# Battery_board_V4_2.net
KiCad netlist of a schematic drawn in EAGLE
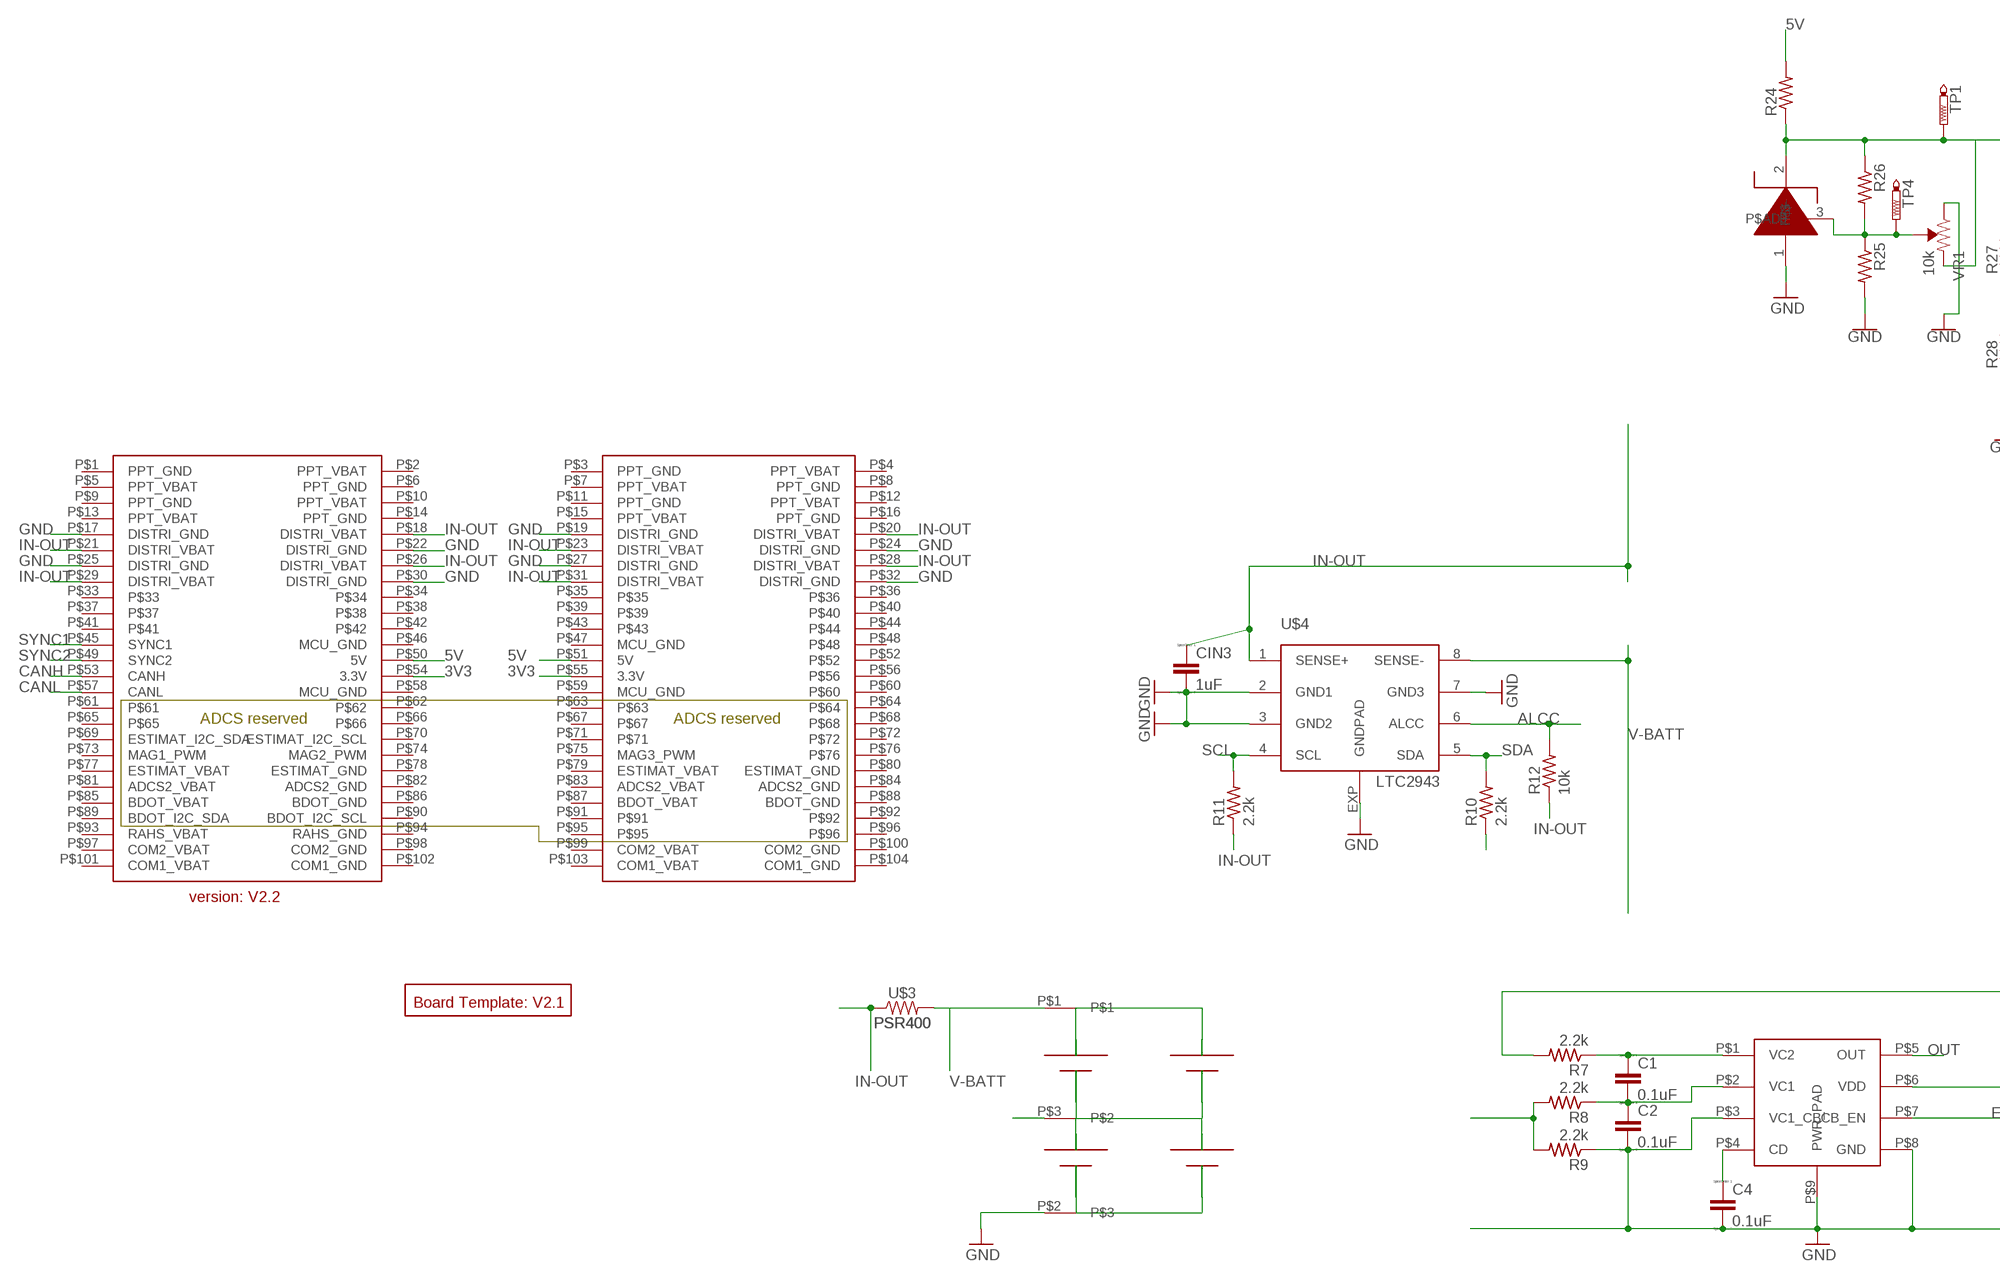
[diagram p0: schematic, sheet 1, part 1 of 2]
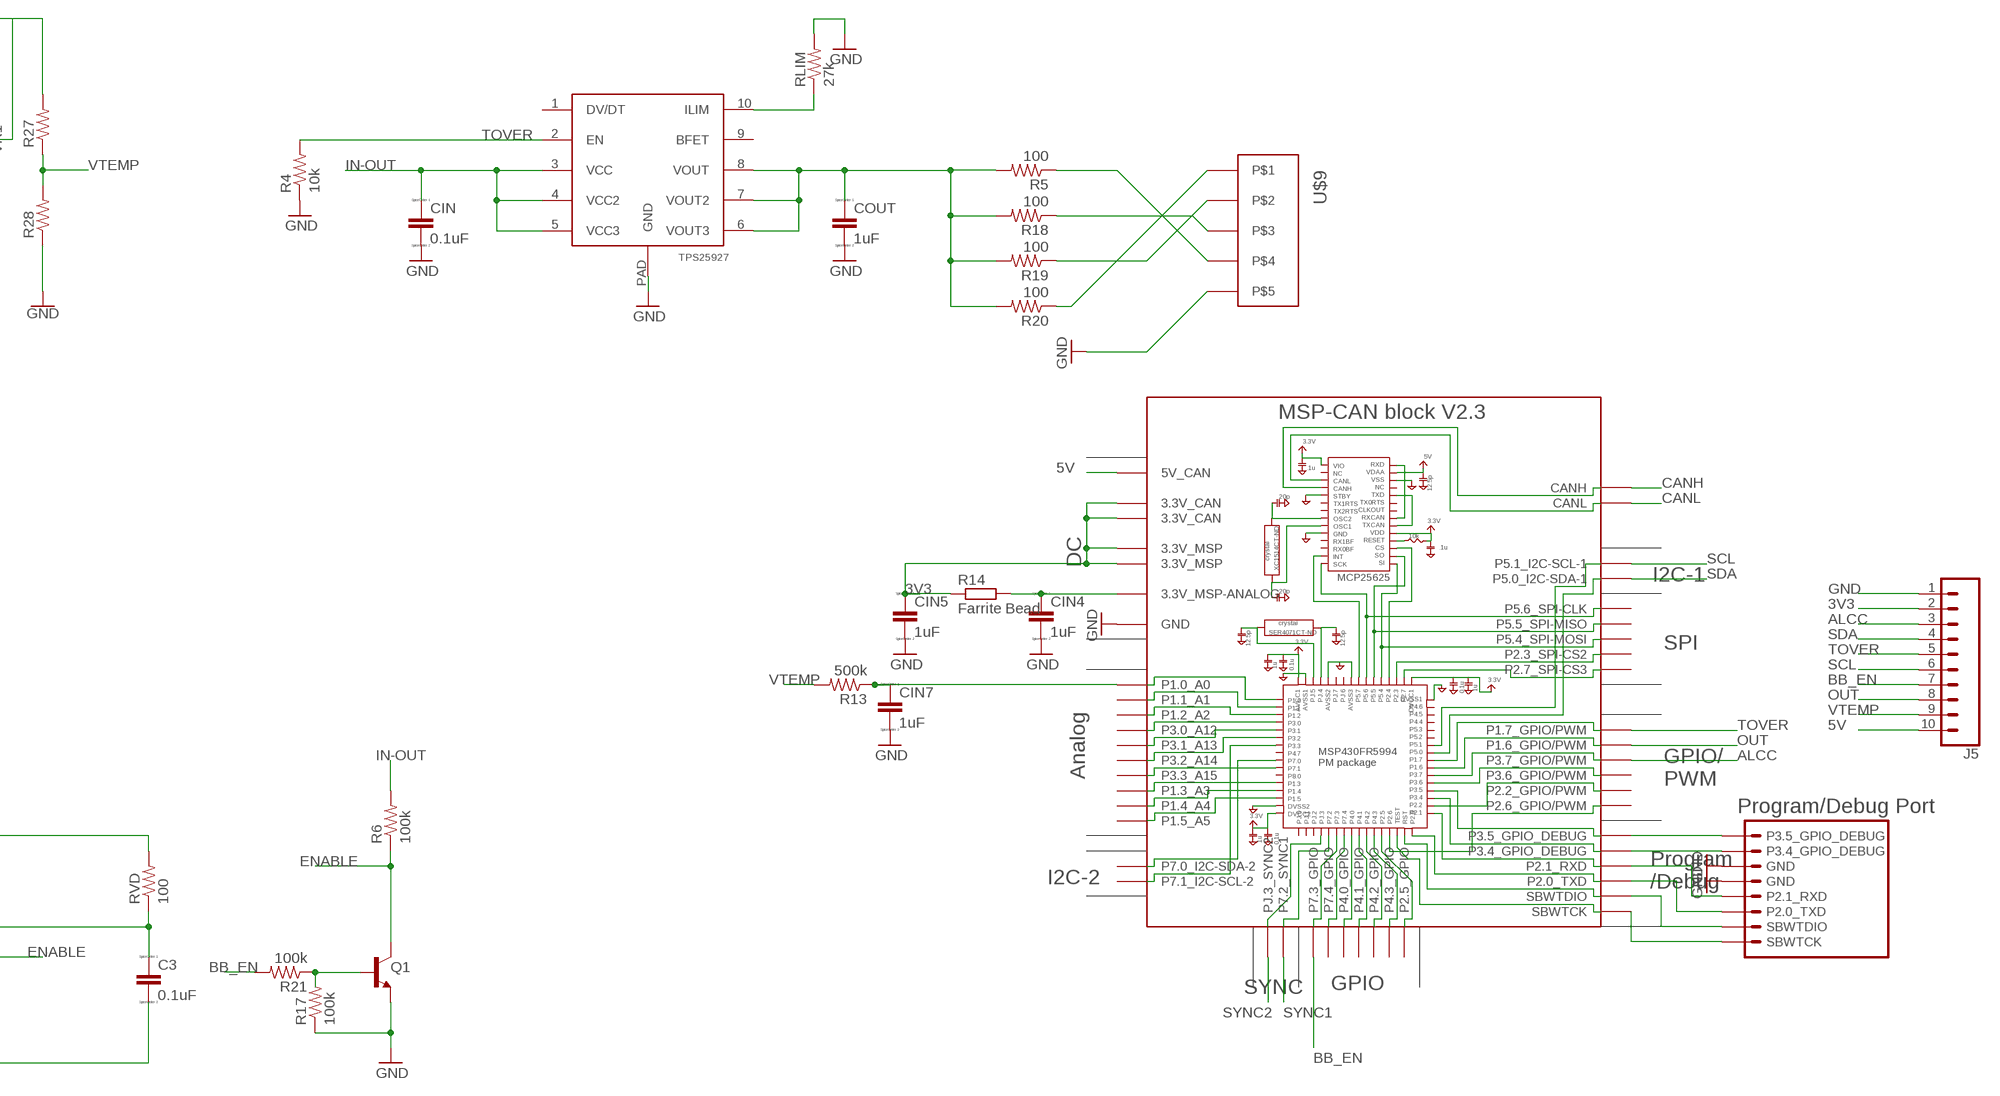
[diagram p1: schematic, sheet 1, part 2 of 2]

(export (version "E")
  (design (tool "Eeschema 10.0.6"))
  (components
    (comp (ref "C1")
      (value "0.1uF")
      (footprint "eagle-import:C0805")
      (libsource (lib "eagle-import") (part "C"))
    )
    (comp (ref "C2")
      (value "0.1uF")
      (footprint "eagle-import:C0805")
      (libsource (lib "eagle-import") (part "C"))
    )
    (comp (ref "C3")
      (value "0.1uF")
      (footprint "eagle-import:C0805")
      (libsource (lib "eagle-import") (part "C"))
    )
    (comp (ref "C4")
      (value "0.1uF")
      (footprint "eagle-import:C0805")
      (libsource (lib "eagle-import") (part "C"))
    )
    (comp (ref "CIN")
      (value "0.1uF")
      (footprint "eagle-import:C0805")
      (libsource (lib "eagle-import") (part "C"))
    )
    (comp (ref "CIN3")
      (value "1uF")
      (footprint "eagle-import:C0805")
      (libsource (lib "eagle-import") (part "C"))
    )
    (comp (ref "CIN4")
      (value "1uF")
      (footprint "eagle-import:C0805")
      (libsource (lib "eagle-import") (part "C"))
    )
    (comp (ref "CIN5")
      (value "1uF")
      (footprint "eagle-import:C0805")
      (libsource (lib "eagle-import") (part "C"))
    )
    (comp (ref "CIN7")
      (value "1uF")
      (footprint "eagle-import:C0805")
      (libsource (lib "eagle-import") (part "C"))
    )
    (comp (ref "COUT")
      (value "1uF")
      (footprint "eagle-import:C0805")
      (libsource (lib "eagle-import") (part "C"))
    )
    (comp (ref "J5")
      (value "CONN_10LOCK")
      (footprint "eagle-import:1X10_LOCK")
      (libsource (lib "eagle-import") (part "CONN_10LOCK"))
    )
    (comp (ref "Q1")
      (value "TRANS_NPN-MMBT2222AL")
      (footprint "eagle-import:SOT23-3")
      (libsource (lib "eagle-import") (part "TRANS_NPN-MMBT2222AL"))
    )
    (comp (ref "R4")
      (value "10k")
      (footprint "eagle-import:R0805")
      (libsource (lib "eagle-import") (part "R-US_R0805"))
    )
    (comp (ref "R5")
      (value "100")
      (footprint "eagle-import:R0805")
      (libsource (lib "eagle-import") (part "R-US_R0805"))
    )
    (comp (ref "R6")
      (value "100k")
      (footprint "eagle-import:R0805")
      (libsource (lib "eagle-import") (part "R-US_R0805"))
    )
    (comp (ref "R7")
      (value "2.2k")
      (footprint "eagle-import:R0805")
      (libsource (lib "eagle-import") (part "R-US_R0805"))
    )
    (comp (ref "R8")
      (value "2.2k")
      (footprint "eagle-import:R0805")
      (libsource (lib "eagle-import") (part "R-US_R0805"))
    )
    (comp (ref "R9")
      (value "2.2k")
      (footprint "eagle-import:R0805")
      (libsource (lib "eagle-import") (part "R-US_R0805"))
    )
    (comp (ref "R10")
      (value "2.2k")
      (footprint "eagle-import:R0805")
      (libsource (lib "eagle-import") (part "R-US_R0805"))
    )
    (comp (ref "R11")
      (value "2.2k")
      (footprint "eagle-import:R0805")
      (libsource (lib "eagle-import") (part "R-US_R0805"))
    )
    (comp (ref "R12")
      (value "10k")
      (footprint "eagle-import:R0805")
      (libsource (lib "eagle-import") (part "R-US_R0805"))
    )
    (comp (ref "R13")
      (value "500k")
      (footprint "eagle-import:R0805")
      (libsource (lib "eagle-import") (part "R-US_R0805"))
    )
    (comp (ref "R14")
      (value "Farrite Bead")
      (footprint "eagle-import:R1206")
      (libsource (lib "eagle-import") (part "R-EU_R1206"))
    )
    (comp (ref "R17")
      (value "100k")
      (footprint "eagle-import:M0805")
      (libsource (lib "eagle-import") (part "R-US_M0805"))
    )
    (comp (ref "R18")
      (value "100")
      (footprint "eagle-import:R0805")
      (libsource (lib "eagle-import") (part "R-US_R0805"))
    )
    (comp (ref "R19")
      (value "100")
      (footprint "eagle-import:R0805")
      (libsource (lib "eagle-import") (part "R-US_R0805"))
    )
    (comp (ref "R20")
      (value "100")
      (footprint "eagle-import:R0805")
      (libsource (lib "eagle-import") (part "R-US_R0805"))
    )
    (comp (ref "R21")
      (value "100k")
      (footprint "eagle-import:M0805")
      (libsource (lib "eagle-import") (part "R-US_M0805"))
    )
    (comp (ref "R24")
      (value "R-US_R0805")
      (footprint "eagle-import:R0805")
      (libsource (lib "eagle-import") (part "R-US_R0805"))
    )
    (comp (ref "R25")
      (value "R-US_R0805")
      (footprint "eagle-import:R0805")
      (libsource (lib "eagle-import") (part "R-US_R0805"))
    )
    (comp (ref "R26")
      (value "R-US_R0805")
      (footprint "eagle-import:R0805")
      (libsource (lib "eagle-import") (part "R-US_R0805"))
    )
    (comp (ref "R27")
      (value "R-US_R0805")
      (footprint "eagle-import:R0805")
      (libsource (lib "eagle-import") (part "R-US_R0805"))
    )
    (comp (ref "R28")
      (value "R-US_R0805")
      (footprint "eagle-import:R0805")
      (libsource (lib "eagle-import") (part "R-US_R0805"))
    )
    (comp (ref "RLIM")
      (value "27k")
      (footprint "eagle-import:R0805")
      (libsource (lib "eagle-import") (part "R-US_R0805"))
    )
    (comp (ref "RVD")
      (value "100")
      (footprint "eagle-import:R0805")
      (libsource (lib "eagle-import") (part "R-US_R0805"))
    )
    (comp (ref "TP1")
      (value "PTR1PAD1-13Y")
      (footprint "eagle-import:P1-13Y")
      (libsource (lib "eagle-import") (part "PTR1PAD1-13Y"))
    )
    (comp (ref "TP4")
      (value "PTR1PAD1-13Y")
      (footprint "eagle-import:P1-13Y")
      (libsource (lib "eagle-import") (part "PTR1PAD1-13Y"))
    )
    (comp (ref "U$1")
      (value "MSP-CAN_BLOCK")
      (footprint "eagle-import:MSP-CAN_BLOCK")
      (libsource (lib "eagle-import") (part "MSP-CAN_BLOCK"))
    )
    (comp (ref "U$2")
      (value "PROGRAM/DEBUG_PORT")
      (footprint "eagle-import:1X08_CONNECTOR")
      (libsource (lib "eagle-import") (part "PROGRAM/DEBUG_PORT"))
    )
    (comp (ref "U$3")
      (value "PSR400")
      (footprint "eagle-import:PSR400")
      (libsource (lib "eagle-import") (part "PSR400"))
    )
    (comp (ref "U$4")
      (value "LTC2943")
      (footprint "eagle-import:DFN8(3X3)LT")
      (libsource (lib "eagle-import") (part "LTC2943"))
    )
    (comp (ref "U$5")
      (value "TPS252927")
      (footprint "eagle-import:VSON10")
      (libsource (lib "eagle-import") (part "TPS252927"))
    )
    (comp (ref "U$6")
      (value "POWER_PACK")
      (footprint "eagle-import:BATTERY_PACK")
      (libsource (lib "eagle-import") (part "POWER_PACK"))
    )
    (comp (ref "U$7")
      (value "PC104_CONNECTOR")
      (footprint "eagle-import:PC104_CONNECTOR")
      (libsource (lib "eagle-import") (part "PC104_CONNECTOR"))
    )
    (comp (ref "U$8")
      (value "BQ29209")
      (footprint "eagle-import:VSON8")
      (libsource (lib "eagle-import") (part "BQ29209"))
    )
    (comp (ref "U$9")
      (value "PICOLOCK_5")
      (footprint "eagle-import:PICOLOCK_5")
      (libsource (lib "eagle-import") (part "PICOLOCK_5"))
    )
    (comp (ref "U$10")
      (value "LM135Z")
      (footprint "eagle-import:TO-92-3")
      (libsource (lib "eagle-import") (part "LM135Z"))
    )
    (comp (ref "U$11")
      (value "BOARD_TEMPLATE")
      (footprint "eagle-import:BOARD_TEMPLATE")
      (libsource (lib "eagle-import") (part "BOARD_TEMPLATE"))
    )
    (comp (ref "VR1")
      (value "10k")
      (footprint "eagle-import:TRIMPOT-SMD-TC33X")
      (libsource (lib "eagle-import") (part "TRIMPOT-SMD-3MM-OPEN-1/10W-25%"))
    )
  )
  (nets
    (net (code "1") (name "/3V3") (class "Default")
      (node (ref "CIN5") (pin "1") (pinfunction "1_1") (pintype "passive"))
      (node (ref "J5") (pin "2") (pinfunction "2_2") (pintype "passive"))
      (node (ref "R14") (pin "1") (pinfunction "1_1") (pintype "passive"))
      (node (ref "U$1") (pin "3.3V@CAN1") (pinfunction "3.3V_CAN_3.3V@CAN1") (pintype "bidirectional"))
      (node (ref "U$1") (pin "3.3V@CAN2") (pinfunction "3.3V_CAN_3.3V@CAN2") (pintype "bidirectional"))
      (node (ref "U$1") (pin "3.3V@MSP1") (pinfunction "3.3V_MSP_3.3V@MSP1") (pintype "bidirectional"))
      (node (ref "U$1") (pin "3.3V@MSP2") (pinfunction "3.3V_MSP_3.3V@MSP2") (pintype "bidirectional"))
      (node (ref "U$7") (pin "P$54") (pinfunction "3.3V_P$54") (pintype "bidirectional"))
      (node (ref "U$7") (pin "P$55") (pinfunction "3.3V_P$55") (pintype "bidirectional"))
    )
    (net (code "2") (name "/5V") (class "Default")
      (node (ref "J5") (pin "10") (pinfunction "10_10") (pintype "passive"))
      (node (ref "R24") (pin "2") (pinfunction "2_2") (pintype "passive"))
      (node (ref "U$1") (pin "5V") (pinfunction "5V_CAN_5V") (pintype "bidirectional"))
      (node (ref "U$7") (pin "P$50") (pinfunction "5V_P$50") (pintype "bidirectional"))
      (node (ref "U$7") (pin "P$51") (pinfunction "5V_P$51") (pintype "bidirectional"))
    )
    (net (code "3") (name "/ALCC") (class "Default")
      (node (ref "J5") (pin "3") (pinfunction "3_3") (pintype "passive"))
      (node (ref "R12") (pin "2") (pinfunction "2_2") (pintype "passive"))
      (node (ref "U$1") (pin "P3.7_GPIO/PWM") (pinfunction "P3.7_GPIO/PWM_P3.7_GPIO/PWM") (pintype "bidirectional"))
      (node (ref "U$4") (pin "6") (pinfunction "ALCC_6") (pintype "bidirectional"))
    )
    (net (code "4") (name "/BB_EN") (class "Default")
      (node (ref "J5") (pin "7") (pinfunction "7_7") (pintype "passive"))
      (node (ref "R21") (pin "2") (pinfunction "2_2") (pintype "passive"))
      (node (ref "U$1") (pin "P7.3_GPIO") (pinfunction "P7.3_GPIO_P7.3_GPIO") (pintype "bidirectional"))
    )
    (net (code "5") (name "/BT-NODE") (class "Default")
      (node (ref "R8") (pin "2") (pinfunction "2_2") (pintype "passive"))
      (node (ref "R9") (pin "2") (pinfunction "2_2") (pintype "passive"))
      (node (ref "U$6") (pin "P$3") (pinfunction "P$2_P$3") (pintype "bidirectional"))
    )
    (net (code "6") (name "/CANH") (class "Default")
      (node (ref "U$1") (pin "CANH") (pinfunction "CANH_CANH") (pintype "bidirectional"))
      (node (ref "U$7") (pin "P$53") (pinfunction "CANH_P$53") (pintype "bidirectional"))
    )
    (net (code "7") (name "/CANL") (class "Default")
      (node (ref "U$1") (pin "CANL") (pinfunction "CANL_CANL") (pintype "bidirectional"))
      (node (ref "U$7") (pin "P$57") (pinfunction "CANL_P$57") (pintype "bidirectional"))
    )
    (net (code "8") (name "/ENABLE") (class "Default")
      (node (ref "Q1") (pin "3") (pinfunction "C_3") (pintype "passive"))
      (node (ref "R6") (pin "1") (pinfunction "1_1") (pintype "passive"))
      (node (ref "U$8") (pin "P$7") (pinfunction "CB_EN_P$7") (pintype "bidirectional"))
    )
    (net (code "9") (name "/IN-OUT") (class "Default")
      (node (ref "CIN") (pin "1") (pinfunction "1_1") (pintype "passive"))
      (node (ref "CIN3") (pin "1") (pinfunction "1_1") (pintype "passive"))
      (node (ref "R10") (pin "1") (pinfunction "1_1") (pintype "passive"))
      (node (ref "R11") (pin "1") (pinfunction "1_1") (pintype "passive"))
      (node (ref "R12") (pin "1") (pinfunction "1_1") (pintype "passive"))
      (node (ref "R6") (pin "2") (pinfunction "2_2") (pintype "passive"))
      (node (ref "R7") (pin "2") (pinfunction "2_2") (pintype "passive"))
      (node (ref "RVD") (pin "2") (pinfunction "2_2") (pintype "passive"))
      (node (ref "U$3") (pin "P$1") (pinfunction "1_P$1") (pintype "passive"))
      (node (ref "U$4") (pin "1") (pinfunction "SENSE+_1") (pintype "bidirectional"))
      (node (ref "U$5") (pin "3") (pinfunction "VCC_3") (pintype "bidirectional"))
      (node (ref "U$5") (pin "4") (pinfunction "VCC2_4") (pintype "bidirectional"))
      (node (ref "U$5") (pin "5") (pinfunction "VCC3_5") (pintype "bidirectional"))
      (node (ref "U$7") (pin "P$18") (pinfunction "DISTRI_VBAT_P$18") (pintype "bidirectional"))
      (node (ref "U$7") (pin "P$20") (pinfunction "DISTRI_VBAT_P$20") (pintype "bidirectional"))
      (node (ref "U$7") (pin "P$21") (pinfunction "DISTRI_VBAT_P$21") (pintype "bidirectional"))
      (node (ref "U$7") (pin "P$23") (pinfunction "DISTRI_VBAT_P$23") (pintype "bidirectional"))
      (node (ref "U$7") (pin "P$26") (pinfunction "DISTRI_VBAT_P$26") (pintype "bidirectional"))
      (node (ref "U$7") (pin "P$28") (pinfunction "DISTRI_VBAT_P$28") (pintype "bidirectional"))
      (node (ref "U$7") (pin "P$29") (pinfunction "DISTRI_VBAT_P$29") (pintype "bidirectional"))
      (node (ref "U$7") (pin "P$31") (pinfunction "DISTRI_VBAT_P$31") (pintype "bidirectional"))
    )
    (net (code "10") (name "/OUT") (class "Default")
      (node (ref "J5") (pin "8") (pinfunction "8_8") (pintype "passive"))
      (node (ref "U$1") (pin "P1.6_GPIO/PWM") (pinfunction "P1.6_GPIO/PWM_P1.6_GPIO/PWM") (pintype "bidirectional"))
      (node (ref "U$8") (pin "P$5") (pinfunction "OUT_P$5") (pintype "bidirectional"))
    )
    (net (code "11") (name "/SCL") (class "Default")
      (node (ref "J5") (pin "6") (pinfunction "6_6") (pintype "passive"))
      (node (ref "R11") (pin "2") (pinfunction "2_2") (pintype "passive"))
      (node (ref "U$1") (pin "P5.1_I2C-SCL-1") (pinfunction "P5.1_I2C-SCL-1_P5.1_I2C-SCL-1") (pintype "bidirectional"))
      (node (ref "U$4") (pin "4") (pinfunction "SCL_4") (pintype "bidirectional"))
    )
    (net (code "12") (name "/SDA") (class "Default")
      (node (ref "J5") (pin "4") (pinfunction "4_4") (pintype "passive"))
      (node (ref "R10") (pin "2") (pinfunction "2_2") (pintype "passive"))
      (node (ref "U$1") (pin "P5.0_I2C-SDA-1") (pinfunction "P5.0_I2C-SDA-1_P5.0_I2C-SDA-1") (pintype "bidirectional"))
      (node (ref "U$4") (pin "5") (pinfunction "SDA_5") (pintype "bidirectional"))
    )
    (net (code "13") (name "/SYNC1") (class "Default")
      (node (ref "U$1") (pin "P7.2_SYNC1") (pinfunction "P7.2_SYNC1_P7.2_SYNC1") (pintype "bidirectional"))
      (node (ref "U$7") (pin "P$45") (pinfunction "SYNC1_P$45") (pintype "bidirectional"))
    )
    (net (code "14") (name "/SYNC2") (class "Default")
      (node (ref "U$1") (pin "PJ.3_SYNC2") (pinfunction "PJ.3_SYNC2_PJ.3_SYNC2") (pintype "bidirectional"))
      (node (ref "U$7") (pin "P$49") (pinfunction "SYNC2_P$49") (pintype "bidirectional"))
    )
    (net (code "15") (name "/TOVER") (class "Default")
      (node (ref "J5") (pin "5") (pinfunction "5_5") (pintype "passive"))
      (node (ref "R4") (pin "2") (pinfunction "2_2") (pintype "passive"))
      (node (ref "U$1") (pin "P1.7_GPIO/PWM") (pinfunction "P1.7_GPIO/PWM_P1.7_GPIO/PWM") (pintype "bidirectional"))
      (node (ref "U$5") (pin "2") (pinfunction "EN_2") (pintype "bidirectional"))
    )
    (net (code "16") (name "/V-BATT") (class "Default")
      (node (ref "U$3") (pin "P$2") (pinfunction "2_P$2") (pintype "passive"))
      (node (ref "U$4") (pin "8") (pinfunction "SENSE-_8") (pintype "bidirectional"))
      (node (ref "U$6") (pin "P$1") (pinfunction "P$1_P$1") (pintype "bidirectional"))
    )
    (net (code "17") (name "/VTEMP") (class "Default")
      (node (ref "J5") (pin "9") (pinfunction "9_9") (pintype "passive"))
      (node (ref "R13") (pin "2") (pinfunction "2_2") (pintype "passive"))
      (node (ref "R27") (pin "1") (pinfunction "1_1") (pintype "passive"))
      (node (ref "R28") (pin "2") (pinfunction "2_2") (pintype "passive"))
    )
    (net (code "18") (name "GND") (class "Default")
      (node (ref "C2") (pin "2") (pinfunction "2_2") (pintype "passive"))
      (node (ref "C3") (pin "2") (pinfunction "2_2") (pintype "passive"))
      (node (ref "C4") (pin "2") (pinfunction "2_2") (pintype "passive"))
      (node (ref "CIN") (pin "2") (pinfunction "2_2") (pintype "passive"))
      (node (ref "CIN3") (pin "2") (pinfunction "2_2") (pintype "passive"))
      (node (ref "CIN4") (pin "2") (pinfunction "2_2") (pintype "passive"))
      (node (ref "CIN5") (pin "2") (pinfunction "2_2") (pintype "passive"))
      (node (ref "CIN7") (pin "2") (pinfunction "2_2") (pintype "passive"))
      (node (ref "COUT") (pin "2") (pinfunction "2_2") (pintype "passive"))
      (node (ref "J5") (pin "1") (pinfunction "1_1") (pintype "passive"))
      (node (ref "Q1") (pin "2") (pinfunction "E_2") (pintype "passive"))
      (node (ref "R17") (pin "1") (pinfunction "1_1") (pintype "passive"))
      (node (ref "R25") (pin "2") (pinfunction "2_2") (pintype "passive"))
      (node (ref "R28") (pin "1") (pinfunction "1_1") (pintype "passive"))
      (node (ref "R4") (pin "1") (pinfunction "1_1") (pintype "passive"))
      (node (ref "R9") (pin "1") (pinfunction "1_1") (pintype "passive"))
      (node (ref "RLIM") (pin "2") (pinfunction "2_2") (pintype "passive"))
      (node (ref "U$1") (pin "GND@1") (pinfunction "GND_GND@1") (pintype "bidirectional"))
      (node (ref "U$1") (pin "GND@10") (pinfunction "GND_GND@10") (pintype "bidirectional"))
      (node (ref "U$1") (pin "GND@11") (pinfunction "GND_GND@11") (pintype "bidirectional"))
      (node (ref "U$1") (pin "GND@12") (pinfunction "GND_GND@12") (pintype "bidirectional"))
      (node (ref "U$1") (pin "GND@13") (pinfunction "GND_GND@13") (pintype "bidirectional"))
      (node (ref "U$1") (pin "GND@14") (pinfunction "GND_GND@14") (pintype "bidirectional"))
      (node (ref "U$1") (pin "GND@15") (pinfunction "GND_GND@15") (pintype "bidirectional"))
      (node (ref "U$1") (pin "GND@16") (pinfunction "GND_GND@16") (pintype "bidirectional"))
      (node (ref "U$1") (pin "GND@17") (pinfunction "GND_GND@17") (pintype "bidirectional"))
      (node (ref "U$1") (pin "GND@2") (pinfunction "GND_GND@2") (pintype "bidirectional"))
      (node (ref "U$1") (pin "GND@26") (pinfunction "GND_GND@26") (pintype "bidirectional"))
      (node (ref "U$1") (pin "GND@3") (pinfunction "GND_GND@3") (pintype "bidirectional"))
      (node (ref "U$1") (pin "GND@4") (pinfunction "GND_GND@4") (pintype "bidirectional"))
      (node (ref "U$1") (pin "GND@5") (pinfunction "GND_GND@5") (pintype "bidirectional"))
      (node (ref "U$1") (pin "GND@7") (pinfunction "GND_GND@7") (pintype "bidirectional"))
      (node (ref "U$1") (pin "GND@8") (pinfunction "GND_GND@8") (pintype "bidirectional"))
      (node (ref "U$1") (pin "GND@9") (pinfunction "GND_GND@9") (pintype "bidirectional"))
      (node (ref "U$10") (pin "1") (pinfunction "P$-_1") (pintype "bidirectional"))
      (node (ref "U$2") (pin "5") (pinfunction "GND_5") (pintype "bidirectional"))
      (node (ref "U$2") (pin "6") (pinfunction "GND_6") (pintype "bidirectional"))
      (node (ref "U$4") (pin "2") (pinfunction "GND1_2") (pintype "bidirectional"))
      (node (ref "U$4") (pin "3") (pinfunction "GND2_3") (pintype "bidirectional"))
      (node (ref "U$4") (pin "7") (pinfunction "GND3_7") (pintype "bidirectional"))
      (node (ref "U$4") (pin "EXP") (pinfunction "GNDPAD_EXP") (pintype "bidirectional"))
      (node (ref "U$5") (pin "PAD") (pinfunction "GND_PAD") (pintype "bidirectional"))
      (node (ref "U$6") (pin "P$2") (pinfunction "P$3_P$2") (pintype "bidirectional"))
      (node (ref "U$7") (pin "P$17") (pinfunction "DISTRI_GND_P$17") (pintype "bidirectional"))
      (node (ref "U$7") (pin "P$19") (pinfunction "DISTRI_GND_P$19") (pintype "bidirectional"))
      (node (ref "U$7") (pin "P$22") (pinfunction "DISTRI_GND_P$22") (pintype "bidirectional"))
      (node (ref "U$7") (pin "P$24") (pinfunction "DISTRI_GND_P$24") (pintype "bidirectional"))
      (node (ref "U$7") (pin "P$25") (pinfunction "DISTRI_GND_P$25") (pintype "bidirectional"))
      (node (ref "U$7") (pin "P$27") (pinfunction "DISTRI_GND_P$27") (pintype "bidirectional"))
      (node (ref "U$7") (pin "P$30") (pinfunction "DISTRI_GND_P$30") (pintype "bidirectional"))
      (node (ref "U$7") (pin "P$32") (pinfunction "DISTRI_GND_P$32") (pintype "bidirectional"))
      (node (ref "U$8") (pin "P$3") (pinfunction "VC1_CB_P$3") (pintype "bidirectional"))
      (node (ref "U$8") (pin "P$8") (pinfunction "GND_P$8") (pintype "bidirectional"))
      (node (ref "U$8") (pin "P$9") (pinfunction "PWR_PAD_P$9") (pintype "bidirectional"))
      (node (ref "U$9") (pin "P$5") (pinfunction "P$5_P$5") (pintype "bidirectional"))
      (node (ref "VR1") (pin "1") (pinfunction "CW_1") (pintype "passive"))
    )
    (net (code "19") (name "Net-(CIN7-Pad1)") (class "Default")
      (node (ref "CIN7") (pin "1") (pinfunction "1_1") (pintype "passive"))
      (node (ref "R13") (pin "1") (pinfunction "1_1") (pintype "passive"))
      (node (ref "U$1") (pin "P1.0_A0") (pinfunction "P1.0_A0_P1.0_A0") (pintype "bidirectional"))
    )
    (net (code "20") (name "Net-(Q1-B)") (class "Default")
      (node (ref "Q1") (pin "1") (pinfunction "B_1") (pintype "passive"))
      (node (ref "R17") (pin "2") (pinfunction "2_2") (pintype "passive"))
      (node (ref "R21") (pin "1") (pinfunction "1_1") (pintype "passive"))
    )
    (net (code "21") (name "Net-(R5-Pad1)") (class "Default")
      (node (ref "R5") (pin "1") (pinfunction "1_1") (pintype "passive"))
      (node (ref "U$9") (pin "P$4") (pinfunction "P$4_P$4") (pintype "bidirectional"))
    )
    (net (code "22") (name "Net-(R18-Pad1)") (class "Default")
      (node (ref "R18") (pin "1") (pinfunction "1_1") (pintype "passive"))
      (node (ref "U$9") (pin "P$3") (pinfunction "P$3_P$3") (pintype "bidirectional"))
    )
    (net (code "23") (name "Net-(R19-Pad1)") (class "Default")
      (node (ref "R19") (pin "1") (pinfunction "1_1") (pintype "passive"))
      (node (ref "U$9") (pin "P$2") (pinfunction "P$2_P$2") (pintype "bidirectional"))
    )
    (net (code "24") (name "Net-(R20-Pad1)") (class "Default")
      (node (ref "R20") (pin "1") (pinfunction "1_1") (pintype "passive"))
      (node (ref "U$9") (pin "P$1") (pinfunction "P$1_P$1") (pintype "bidirectional"))
    )
    (net (code "25") (name "Net-(U$1-3.3V_MSP-ANALOG)") (class "Default")
      (node (ref "CIN4") (pin "1") (pinfunction "1_1") (pintype "passive"))
      (node (ref "R14") (pin "2") (pinfunction "2_2") (pintype "passive"))
      (node (ref "U$1") (pin "3.3V_ANALOG@MSP2") (pinfunction "3.3V_MSP-ANALOG_3.3V_ANALOG@MSP2") (pintype "bidirectional"))
    )
    (net (code "26") (name "Net-(U$1-PadSBWTCK)") (class "Default")
      (node (ref "U$1") (pin "SBWTCK") (pinfunction "SBWTCK_SBWTCK") (pintype "bidirectional"))
      (node (ref "U$2") (pin "SBWTCK") (pinfunction "SBWTCK_SBWTCK") (pintype "bidirectional"))
    )
    (net (code "27") (name "Net-(U$2-P2.0_TXD)") (class "Default")
      (node (ref "U$1") (pin "P2.0_TXD") (pinfunction "P2.0_TXD_P2.0_TXD") (pintype "bidirectional"))
      (node (ref "U$2") (pin "3") (pinfunction "P2.0_TXD_3") (pintype "bidirectional"))
    )
    (net (code "28") (name "Net-(U$2-P2.1_RXD)") (class "Default")
      (node (ref "U$1") (pin "P2.1_RXD") (pinfunction "P2.1_RXD_P2.1_RXD") (pintype "bidirectional"))
      (node (ref "U$2") (pin "4") (pinfunction "P2.1_RXD_4") (pintype "bidirectional"))
    )
    (net (code "29") (name "Net-(U$2-P3.4_GPIO_DEBUG)") (class "Default")
      (node (ref "U$1") (pin "P3.4_GPIO_DEBUG") (pinfunction "P3.4_GPIO_DEBUG_P3.4_GPIO_DEBUG") (pintype "bidirectional"))
      (node (ref "U$2") (pin "7") (pinfunction "P3.4_GPIO_DEBUG_7") (pintype "bidirectional"))
    )
    (net (code "30") (name "Net-(U$2-P3.5_GPIO_DEBUG)") (class "Default")
      (node (ref "U$1") (pin "P3.5_GPIO_DEBUG") (pinfunction "P3.5_GPIO_DEBUG_P3.5_GPIO_DEBUG") (pintype "bidirectional"))
      (node (ref "U$2") (pin "8") (pinfunction "P3.5_GPIO_DEBUG_8") (pintype "bidirectional"))
    )
    (net (code "31") (name "Net-(U$2-SBWTDIO)") (class "Default")
      (node (ref "U$1") (pin "SBWTDIO") (pinfunction "SBWTDIO_SBWTDIO") (pintype "bidirectional"))
      (node (ref "U$2") (pin "2") (pinfunction "SBWTDIO_2") (pintype "bidirectional"))
    )
    (net (code "32") (name "Net-(U$5-ILIM)") (class "Default")
      (node (ref "RLIM") (pin "1") (pinfunction "1_1") (pintype "passive"))
      (node (ref "U$5") (pin "10") (pinfunction "ILIM_10") (pintype "bidirectional"))
    )
    (net (code "33") (name "Net-(U$5-VOUT)") (class "Default")
      (node (ref "COUT") (pin "1") (pinfunction "1_1") (pintype "passive"))
      (node (ref "R18") (pin "2") (pinfunction "2_2") (pintype "passive"))
      (node (ref "R19") (pin "2") (pinfunction "2_2") (pintype "passive"))
      (node (ref "R20") (pin "2") (pinfunction "2_2") (pintype "passive"))
      (node (ref "R5") (pin "2") (pinfunction "2_2") (pintype "passive"))
      (node (ref "U$5") (pin "6") (pinfunction "VOUT3_6") (pintype "bidirectional"))
      (node (ref "U$5") (pin "7") (pinfunction "VOUT2_7") (pintype "bidirectional"))
      (node (ref "U$5") (pin "8") (pinfunction "VOUT_8") (pintype "bidirectional"))
    )
    (net (code "34") (name "Net-(U$8-CD)") (class "Default")
      (node (ref "C4") (pin "1") (pinfunction "1_1") (pintype "passive"))
      (node (ref "U$8") (pin "P$4") (pinfunction "CD_P$4") (pintype "bidirectional"))
    )
    (net (code "35") (name "Net-(U$8-VC1)") (class "Default")
      (node (ref "C1") (pin "2") (pinfunction "2_2") (pintype "passive"))
      (node (ref "C2") (pin "1") (pinfunction "1_1") (pintype "passive"))
      (node (ref "R8") (pin "1") (pinfunction "1_1") (pintype "passive"))
      (node (ref "U$8") (pin "P$2") (pinfunction "VC1_P$2") (pintype "bidirectional"))
    )
    (net (code "36") (name "Net-(U$8-VC2)") (class "Default")
      (node (ref "C1") (pin "1") (pinfunction "1_1") (pintype "passive"))
      (node (ref "R7") (pin "1") (pinfunction "1_1") (pintype "passive"))
      (node (ref "U$8") (pin "P$1") (pinfunction "VC2_P$1") (pintype "bidirectional"))
    )
    (net (code "37") (name "Net-(U$8-VDD)") (class "Default")
      (node (ref "C3") (pin "1") (pinfunction "1_1") (pintype "passive"))
      (node (ref "RVD") (pin "1") (pinfunction "1_1") (pintype "passive"))
      (node (ref "U$8") (pin "P$6") (pinfunction "VDD_P$6") (pintype "bidirectional"))
    )
    (net (code "38") (name "Net-(U$10-P$+)") (class "Default")
      (node (ref "R24") (pin "1") (pinfunction "1_1") (pintype "passive"))
      (node (ref "R26") (pin "1") (pinfunction "1_1") (pintype "passive"))
      (node (ref "R27") (pin "2") (pinfunction "2_2") (pintype "passive"))
      (node (ref "TP1") (pin "TP") (pinfunction "TP_TP") (pintype "input"))
      (node (ref "U$10") (pin "2") (pinfunction "P$+_2") (pintype "bidirectional"))
      (node (ref "VR1") (pin "3") (pinfunction "CCW_3") (pintype "passive"))
    )
    (net (code "39") (name "Net-(U$10-P$ADJ)") (class "Default")
      (node (ref "R25") (pin "1") (pinfunction "1_1") (pintype "passive"))
      (node (ref "R26") (pin "2") (pinfunction "2_2") (pintype "passive"))
      (node (ref "TP4") (pin "TP") (pinfunction "TP_TP") (pintype "input"))
      (node (ref "U$10") (pin "3") (pinfunction "P$ADJ_3") (pintype "bidirectional"))
      (node (ref "VR1") (pin "2") (pinfunction "WIPER_2") (pintype "passive"))
    )
    (net (code "40") (name "unconnected-(U$1-P2.3_SPI-CS2-PadP2.4_SPI-CS2)") (class "Default")
      (node (ref "U$1") (pin "P2.4_SPI-CS2") (pinfunction "P2.3_SPI-CS2_P2.4_SPI-CS2") (pintype "bidirectional"))
    )
    (net (code "41") (name "unconnected-(U$1-PadP1.1_A1)") (class "Default")
      (node (ref "U$1") (pin "P1.1_A1") (pinfunction "P1.1_A1_P1.1_A1") (pintype "bidirectional"))
    )
    (net (code "42") (name "unconnected-(U$1-PadP1.2_A2)") (class "Default")
      (node (ref "U$1") (pin "P1.2_A2") (pinfunction "P1.2_A2_P1.2_A2") (pintype "bidirectional"))
    )
    (net (code "43") (name "unconnected-(U$1-PadP1.3_A3)") (class "Default")
      (node (ref "U$1") (pin "P1.3_A3") (pinfunction "P1.3_A3_P1.3_A3") (pintype "bidirectional"))
    )
    (net (code "44") (name "unconnected-(U$1-PadP1.4_A4)") (class "Default")
      (node (ref "U$1") (pin "P1.4_A4") (pinfunction "P1.4_A4_P1.4_A4") (pintype "bidirectional"))
    )
    (net (code "45") (name "unconnected-(U$1-PadP1.5_A5)") (class "Default")
      (node (ref "U$1") (pin "P1.5_A5") (pinfunction "P1.5_A5_P1.5_A5") (pintype "bidirectional"))
    )
    (net (code "46") (name "unconnected-(U$1-PadP2.2_GPIO{slash}PWM)") (class "Default")
      (node (ref "U$1") (pin "P2.2_GPIO/PWM") (pinfunction "P2.2_GPIO/PWM_P2.2_GPIO/PWM") (pintype "bidirectional"))
    )
    (net (code "47") (name "unconnected-(U$1-PadP2.5_GPIO)") (class "Default")
      (node (ref "U$1") (pin "P2.5_GPIO") (pinfunction "P2.5_GPIO_P2.5_GPIO") (pintype "bidirectional"))
    )
    (net (code "48") (name "unconnected-(U$1-PadP2.6_GPIO{slash}PWM)") (class "Default")
      (node (ref "U$1") (pin "P2.6_GPIO/PWM") (pinfunction "P2.6_GPIO/PWM_P2.6_GPIO/PWM") (pintype "bidirectional"))
    )
    (net (code "49") (name "unconnected-(U$1-PadP2.7_SPI-CS3)") (class "Default")
      (node (ref "U$1") (pin "P2.7_SPI-CS3") (pinfunction "P2.7_SPI-CS3_P2.7_SPI-CS3") (pintype "bidirectional"))
    )
    (net (code "50") (name "unconnected-(U$1-PadP3.0_A12)") (class "Default")
      (node (ref "U$1") (pin "P3.0_A12") (pinfunction "P3.0_A12_P3.0_A12") (pintype "bidirectional"))
    )
    (net (code "51") (name "unconnected-(U$1-PadP3.1_A13)") (class "Default")
      (node (ref "U$1") (pin "P3.1_A13") (pinfunction "P3.1_A13_P3.1_A13") (pintype "bidirectional"))
    )
    (net (code "52") (name "unconnected-(U$1-PadP3.2_A14)") (class "Default")
      (node (ref "U$1") (pin "P3.2_A14") (pinfunction "P3.2_A14_P3.2_A14") (pintype "bidirectional"))
    )
    (net (code "53") (name "unconnected-(U$1-PadP3.3_A15)") (class "Default")
      (node (ref "U$1") (pin "P3.3_A15") (pinfunction "P3.3_A15_P3.3_A15") (pintype "bidirectional"))
    )
    (net (code "54") (name "unconnected-(U$1-PadP3.6_GPIO{slash}PWM)") (class "Default")
      (node (ref "U$1") (pin "P3.6_GPIO/PWM") (pinfunction "P3.6_GPIO/PWM_P3.6_GPIO/PWM") (pintype "bidirectional"))
    )
    (net (code "55") (name "unconnected-(U$1-PadP4.0_GPIO)") (class "Default")
      (node (ref "U$1") (pin "P4.0_GPIO") (pinfunction "P4.0_GPIO_P4.0_GPIO") (pintype "bidirectional"))
    )
    (net (code "56") (name "unconnected-(U$1-PadP4.1_GPIO)") (class "Default")
      (node (ref "U$1") (pin "P4.1_GPIO") (pinfunction "P4.1_GPIO_P4.1_GPIO") (pintype "bidirectional"))
    )
    (net (code "57") (name "unconnected-(U$1-PadP4.2_GPIO)") (class "Default")
      (node (ref "U$1") (pin "P4.2_GPIO") (pinfunction "P4.2_GPIO_P4.2_GPIO") (pintype "bidirectional"))
    )
    (net (code "58") (name "unconnected-(U$1-PadP4.3_GPIO)") (class "Default")
      (node (ref "U$1") (pin "P4.3_GPIO") (pinfunction "P4.3_GPIO_P4.3_GPIO") (pintype "bidirectional"))
    )
    (net (code "59") (name "unconnected-(U$1-PadP5.4_SPI-MOSI)") (class "Default")
      (node (ref "U$1") (pin "P5.4_SPI-MOSI") (pinfunction "P5.4_SPI-MOSI_P5.4_SPI-MOSI") (pintype "bidirectional"))
    )
    (net (code "60") (name "unconnected-(U$1-PadP5.5_SPI-MISO)") (class "Default")
      (node (ref "U$1") (pin "P5.5_SPI-MISO") (pinfunction "P5.5_SPI-MISO_P5.5_SPI-MISO") (pintype "bidirectional"))
    )
    (net (code "61") (name "unconnected-(U$1-PadP5.6_SPI-CLK)") (class "Default")
      (node (ref "U$1") (pin "P5.6_SPI-CLK") (pinfunction "P5.6_SPI-CLK_P5.6_SPI-CLK") (pintype "bidirectional"))
    )
    (net (code "62") (name "unconnected-(U$1-PadP7.0_I2C-SDA-2)") (class "Default")
      (node (ref "U$1") (pin "P7.0_I2C-SDA-2") (pinfunction "P7.0_I2C-SDA-2_P7.0_I2C-SDA-2") (pintype "bidirectional"))
    )
    (net (code "63") (name "unconnected-(U$1-PadP7.1_I2C-SCL-2)") (class "Default")
      (node (ref "U$1") (pin "P7.1_I2C-SCL-2") (pinfunction "P7.1_I2C-SCL-2_P7.1_I2C-SCL-2") (pintype "bidirectional"))
    )
    (net (code "64") (name "unconnected-(U$1-PadP7.4_GPIO)") (class "Default")
      (node (ref "U$1") (pin "P7.4_GPIO") (pinfunction "P7.4_GPIO_P7.4_GPIO") (pintype "bidirectional"))
    )
    (net (code "65") (name "unconnected-(U$5-BFET-Pad9)") (class "Default")
      (node (ref "U$5") (pin "9") (pinfunction "BFET_9") (pintype "bidirectional"))
    )
    (net (code "66") (name "unconnected-(U$5-DV{slash}DT-Pad1)") (class "Default")
      (node (ref "U$5") (pin "1") (pinfunction "DV/DT_1") (pintype "bidirectional"))
    )
    (net (code "67") (name "unconnected-(U$7-ADCS2_GND-PadP$82)") (class "Default")
      (node (ref "U$7") (pin "P$82") (pinfunction "ADCS2_GND_P$82") (pintype "bidirectional"))
    )
    (net (code "68") (name "unconnected-(U$7-ADCS2_GND-PadP$84)") (class "Default")
      (node (ref "U$7") (pin "P$84") (pinfunction "ADCS2_GND_P$84") (pintype "bidirectional"))
    )
    (net (code "69") (name "unconnected-(U$7-ADCS2_VBAT-PadP$81)") (class "Default")
      (node (ref "U$7") (pin "P$81") (pinfunction "ADCS2_VBAT_P$81") (pintype "bidirectional"))
    )
    (net (code "70") (name "unconnected-(U$7-ADCS2_VBAT-PadP$83)") (class "Default")
      (node (ref "U$7") (pin "P$83") (pinfunction "ADCS2_VBAT_P$83") (pintype "bidirectional"))
    )
    (net (code "71") (name "unconnected-(U$7-BDOT_GND-PadP$86)") (class "Default")
      (node (ref "U$7") (pin "P$86") (pinfunction "BDOT_GND_P$86") (pintype "bidirectional"))
    )
    (net (code "72") (name "unconnected-(U$7-BDOT_GND-PadP$88)") (class "Default")
      (node (ref "U$7") (pin "P$88") (pinfunction "BDOT_GND_P$88") (pintype "bidirectional"))
    )
    (net (code "73") (name "unconnected-(U$7-BDOT_I2C_SCL-PadP$90)") (class "Default")
      (node (ref "U$7") (pin "P$90") (pinfunction "BDOT_I2C_SCL_P$90") (pintype "bidirectional"))
    )
    (net (code "74") (name "unconnected-(U$7-BDOT_I2C_SDA-PadP$89)") (class "Default")
      (node (ref "U$7") (pin "P$89") (pinfunction "BDOT_I2C_SDA_P$89") (pintype "bidirectional"))
    )
    (net (code "75") (name "unconnected-(U$7-BDOT_VBAT-PadP$85)") (class "Default")
      (node (ref "U$7") (pin "P$85") (pinfunction "BDOT_VBAT_P$85") (pintype "bidirectional"))
    )
    (net (code "76") (name "unconnected-(U$7-BDOT_VBAT-PadP$87)") (class "Default")
      (node (ref "U$7") (pin "P$87") (pinfunction "BDOT_VBAT_P$87") (pintype "bidirectional"))
    )
    (net (code "77") (name "unconnected-(U$7-COM1_GND-PadP$102)") (class "Default")
      (node (ref "U$7") (pin "P$102") (pinfunction "COM1_GND_P$102") (pintype "bidirectional"))
    )
    (net (code "78") (name "unconnected-(U$7-COM1_GND-PadP$104)") (class "Default")
      (node (ref "U$7") (pin "P$104") (pinfunction "COM1_GND_P$104") (pintype "bidirectional"))
    )
    (net (code "79") (name "unconnected-(U$7-COM1_VBAT-PadP$101)") (class "Default")
      (node (ref "U$7") (pin "P$101") (pinfunction "COM1_VBAT_P$101") (pintype "bidirectional"))
    )
    (net (code "80") (name "unconnected-(U$7-COM1_VBAT-PadP$103)") (class "Default")
      (node (ref "U$7") (pin "P$103") (pinfunction "COM1_VBAT_P$103") (pintype "bidirectional"))
    )
    (net (code "81") (name "unconnected-(U$7-COM2_GND-PadP$98)") (class "Default")
      (node (ref "U$7") (pin "P$98") (pinfunction "COM2_GND_P$98") (pintype "bidirectional"))
    )
    (net (code "82") (name "unconnected-(U$7-COM2_GND-PadP$100)") (class "Default")
      (node (ref "U$7") (pin "P$100") (pinfunction "COM2_GND_P$100") (pintype "bidirectional"))
    )
    (net (code "83") (name "unconnected-(U$7-COM2_VBAT-PadP$97)") (class "Default")
      (node (ref "U$7") (pin "P$97") (pinfunction "COM2_VBAT_P$97") (pintype "bidirectional"))
    )
    (net (code "84") (name "unconnected-(U$7-COM2_VBAT-PadP$99)") (class "Default")
      (node (ref "U$7") (pin "P$99") (pinfunction "COM2_VBAT_P$99") (pintype "bidirectional"))
    )
    (net (code "85") (name "unconnected-(U$7-ESTIMAT_GND-PadP$78)") (class "Default")
      (node (ref "U$7") (pin "P$78") (pinfunction "ESTIMAT_GND_P$78") (pintype "bidirectional"))
    )
    (net (code "86") (name "unconnected-(U$7-ESTIMAT_GND-PadP$80)") (class "Default")
      (node (ref "U$7") (pin "P$80") (pinfunction "ESTIMAT_GND_P$80") (pintype "bidirectional"))
    )
    (net (code "87") (name "unconnected-(U$7-ESTIMAT_I2C_SCL-PadP$70)") (class "Default")
      (node (ref "U$7") (pin "P$70") (pinfunction "ESTIMAT_I2C_SCL_P$70") (pintype "bidirectional"))
    )
    (net (code "88") (name "unconnected-(U$7-ESTIMAT_I2C_SDA-PadP$69)") (class "Default")
      (node (ref "U$7") (pin "P$69") (pinfunction "ESTIMAT_I2C_SDA_P$69") (pintype "bidirectional"))
    )
    (net (code "89") (name "unconnected-(U$7-ESTIMAT_VBAT-PadP$77)") (class "Default")
      (node (ref "U$7") (pin "P$77") (pinfunction "ESTIMAT_VBAT_P$77") (pintype "bidirectional"))
    )
    (net (code "90") (name "unconnected-(U$7-ESTIMAT_VBAT-PadP$79)") (class "Default")
      (node (ref "U$7") (pin "P$79") (pinfunction "ESTIMAT_VBAT_P$79") (pintype "bidirectional"))
    )
    (net (code "91") (name "unconnected-(U$7-MAG1_PWM-PadP$73)") (class "Default")
      (node (ref "U$7") (pin "P$73") (pinfunction "MAG1_PWM_P$73") (pintype "bidirectional"))
    )
    (net (code "92") (name "unconnected-(U$7-MAG2_PWM-PadP$74)") (class "Default")
      (node (ref "U$7") (pin "P$74") (pinfunction "MAG2_PWM_P$74") (pintype "bidirectional"))
    )
    (net (code "93") (name "unconnected-(U$7-MAG3_PWM-PadP$75)") (class "Default")
      (node (ref "U$7") (pin "P$75") (pinfunction "MAG3_PWM_P$75") (pintype "bidirectional"))
    )
    (net (code "94") (name "unconnected-(U$7-MCU_GND-PadP$46)") (class "Default")
      (node (ref "U$7") (pin "P$46") (pinfunction "MCU_GND_P$46") (pintype "bidirectional"))
    )
    (net (code "95") (name "unconnected-(U$7-MCU_GND-PadP$47)") (class "Default")
      (node (ref "U$7") (pin "P$47") (pinfunction "MCU_GND_P$47") (pintype "bidirectional"))
    )
    (net (code "96") (name "unconnected-(U$7-MCU_GND-PadP$58)") (class "Default")
      (node (ref "U$7") (pin "P$58") (pinfunction "MCU_GND_P$58") (pintype "bidirectional"))
    )
    (net (code "97") (name "unconnected-(U$7-MCU_GND-PadP$59)") (class "Default")
      (node (ref "U$7") (pin "P$59") (pinfunction "MCU_GND_P$59") (pintype "bidirectional"))
    )
    (net (code "98") (name "unconnected-(U$7-PPT_GND-PadP$1)") (class "Default")
      (node (ref "U$7") (pin "P$1") (pinfunction "PPT_GND_P$1") (pintype "bidirectional"))
    )
    (net (code "99") (name "unconnected-(U$7-PPT_GND-PadP$3)") (class "Default")
      (node (ref "U$7") (pin "P$3") (pinfunction "PPT_GND_P$3") (pintype "bidirectional"))
    )
    (net (code "100") (name "unconnected-(U$7-PPT_GND-PadP$6)") (class "Default")
      (node (ref "U$7") (pin "P$6") (pinfunction "PPT_GND_P$6") (pintype "bidirectional"))
    )
    (net (code "101") (name "unconnected-(U$7-PPT_GND-PadP$8)") (class "Default")
      (node (ref "U$7") (pin "P$8") (pinfunction "PPT_GND_P$8") (pintype "bidirectional"))
    )
    (net (code "102") (name "unconnected-(U$7-PPT_GND-PadP$9)") (class "Default")
      (node (ref "U$7") (pin "P$9") (pinfunction "PPT_GND_P$9") (pintype "bidirectional"))
    )
    (net (code "103") (name "unconnected-(U$7-PPT_GND-PadP$11)") (class "Default")
      (node (ref "U$7") (pin "P$11") (pinfunction "PPT_GND_P$11") (pintype "bidirectional"))
    )
    (net (code "104") (name "unconnected-(U$7-PPT_GND-PadP$14)") (class "Default")
      (node (ref "U$7") (pin "P$14") (pinfunction "PPT_GND_P$14") (pintype "bidirectional"))
    )
    (net (code "105") (name "unconnected-(U$7-PPT_GND-PadP$16)") (class "Default")
      (node (ref "U$7") (pin "P$16") (pinfunction "PPT_GND_P$16") (pintype "bidirectional"))
    )
    (net (code "106") (name "unconnected-(U$7-PPT_VBAT-PadP$2)") (class "Default")
      (node (ref "U$7") (pin "P$2") (pinfunction "PPT_VBAT_P$2") (pintype "bidirectional"))
    )
    (net (code "107") (name "unconnected-(U$7-PPT_VBAT-PadP$4)") (class "Default")
      (node (ref "U$7") (pin "P$4") (pinfunction "PPT_VBAT_P$4") (pintype "bidirectional"))
    )
    (net (code "108") (name "unconnected-(U$7-PPT_VBAT-PadP$5)") (class "Default")
      (node (ref "U$7") (pin "P$5") (pinfunction "PPT_VBAT_P$5") (pintype "bidirectional"))
    )
    (net (code "109") (name "unconnected-(U$7-PPT_VBAT-PadP$7)") (class "Default")
      (node (ref "U$7") (pin "P$7") (pinfunction "PPT_VBAT_P$7") (pintype "bidirectional"))
    )
    (net (code "110") (name "unconnected-(U$7-PPT_VBAT-PadP$10)") (class "Default")
      (node (ref "U$7") (pin "P$10") (pinfunction "PPT_VBAT_P$10") (pintype "bidirectional"))
    )
    (net (code "111") (name "unconnected-(U$7-PPT_VBAT-PadP$12)") (class "Default")
      (node (ref "U$7") (pin "P$12") (pinfunction "PPT_VBAT_P$12") (pintype "bidirectional"))
    )
    (net (code "112") (name "unconnected-(U$7-PPT_VBAT-PadP$13)") (class "Default")
      (node (ref "U$7") (pin "P$13") (pinfunction "PPT_VBAT_P$13") (pintype "bidirectional"))
    )
    (net (code "113") (name "unconnected-(U$7-PPT_VBAT-PadP$15)") (class "Default")
      (node (ref "U$7") (pin "P$15") (pinfunction "PPT_VBAT_P$15") (pintype "bidirectional"))
    )
    (net (code "114") (name "unconnected-(U$7-PadP$33)") (class "Default")
      (node (ref "U$7") (pin "P$33") (pinfunction "P$33_P$33") (pintype "bidirectional"))
    )
    (net (code "115") (name "unconnected-(U$7-PadP$34)") (class "Default")
      (node (ref "U$7") (pin "P$34") (pinfunction "P$34_P$34") (pintype "bidirectional"))
    )
    (net (code "116") (name "unconnected-(U$7-PadP$35)") (class "Default")
      (node (ref "U$7") (pin "P$35") (pinfunction "P$35_P$35") (pintype "bidirectional"))
    )
    (net (code "117") (name "unconnected-(U$7-PadP$36)") (class "Default")
      (node (ref "U$7") (pin "P$36") (pinfunction "P$36_P$36") (pintype "bidirectional"))
    )
    (net (code "118") (name "unconnected-(U$7-PadP$37)") (class "Default")
      (node (ref "U$7") (pin "P$37") (pinfunction "P$37_P$37") (pintype "bidirectional"))
    )
    (net (code "119") (name "unconnected-(U$7-PadP$38)") (class "Default")
      (node (ref "U$7") (pin "P$38") (pinfunction "P$38_P$38") (pintype "bidirectional"))
    )
    (net (code "120") (name "unconnected-(U$7-PadP$39)") (class "Default")
      (node (ref "U$7") (pin "P$39") (pinfunction "P$39_P$39") (pintype "bidirectional"))
    )
    (net (code "121") (name "unconnected-(U$7-PadP$40)") (class "Default")
      (node (ref "U$7") (pin "P$40") (pinfunction "P$40_P$40") (pintype "bidirectional"))
    )
    (net (code "122") (name "unconnected-(U$7-PadP$41)") (class "Default")
      (node (ref "U$7") (pin "P$41") (pinfunction "P$41_P$41") (pintype "bidirectional"))
    )
    (net (code "123") (name "unconnected-(U$7-PadP$42)") (class "Default")
      (node (ref "U$7") (pin "P$42") (pinfunction "P$42_P$42") (pintype "bidirectional"))
    )
    (net (code "124") (name "unconnected-(U$7-PadP$43)") (class "Default")
      (node (ref "U$7") (pin "P$43") (pinfunction "P$43_P$43") (pintype "bidirectional"))
    )
    (net (code "125") (name "unconnected-(U$7-PadP$44)") (class "Default")
      (node (ref "U$7") (pin "P$44") (pinfunction "P$44_P$44") (pintype "bidirectional"))
    )
    (net (code "126") (name "unconnected-(U$7-PadP$48)") (class "Default")
      (node (ref "U$7") (pin "P$48") (pinfunction "P$48_P$48") (pintype "bidirectional"))
    )
    (net (code "127") (name "unconnected-(U$7-PadP$52)") (class "Default")
      (node (ref "U$7") (pin "P$52") (pinfunction "P$52_P$52") (pintype "bidirectional"))
    )
    (net (code "128") (name "unconnected-(U$7-PadP$56)") (class "Default")
      (node (ref "U$7") (pin "P$56") (pinfunction "P$56_P$56") (pintype "bidirectional"))
    )
    (net (code "129") (name "unconnected-(U$7-PadP$60)") (class "Default")
      (node (ref "U$7") (pin "P$60") (pinfunction "P$60_P$60") (pintype "bidirectional"))
    )
    (net (code "130") (name "unconnected-(U$7-PadP$61)") (class "Default")
      (node (ref "U$7") (pin "P$61") (pinfunction "P$61_P$61") (pintype "bidirectional"))
    )
    (net (code "131") (name "unconnected-(U$7-PadP$62)") (class "Default")
      (node (ref "U$7") (pin "P$62") (pinfunction "P$62_P$62") (pintype "bidirectional"))
    )
    (net (code "132") (name "unconnected-(U$7-PadP$63)") (class "Default")
      (node (ref "U$7") (pin "P$63") (pinfunction "P$63_P$63") (pintype "bidirectional"))
    )
    (net (code "133") (name "unconnected-(U$7-PadP$64)") (class "Default")
      (node (ref "U$7") (pin "P$64") (pinfunction "P$64_P$64") (pintype "bidirectional"))
    )
    (net (code "134") (name "unconnected-(U$7-PadP$65)") (class "Default")
      (node (ref "U$7") (pin "P$65") (pinfunction "P$65_P$65") (pintype "bidirectional"))
    )
    (net (code "135") (name "unconnected-(U$7-PadP$66)") (class "Default")
      (node (ref "U$7") (pin "P$66") (pinfunction "P$66_P$66") (pintype "bidirectional"))
    )
    (net (code "136") (name "unconnected-(U$7-PadP$67)") (class "Default")
      (node (ref "U$7") (pin "P$67") (pinfunction "P$67_P$67") (pintype "bidirectional"))
    )
    (net (code "137") (name "unconnected-(U$7-PadP$68)") (class "Default")
      (node (ref "U$7") (pin "P$68") (pinfunction "P$68_P$68") (pintype "bidirectional"))
    )
    (net (code "138") (name "unconnected-(U$7-PadP$71)") (class "Default")
      (node (ref "U$7") (pin "P$71") (pinfunction "P$71_P$71") (pintype "bidirectional"))
    )
    (net (code "139") (name "unconnected-(U$7-PadP$72)") (class "Default")
      (node (ref "U$7") (pin "P$72") (pinfunction "P$72_P$72") (pintype "bidirectional"))
    )
    (net (code "140") (name "unconnected-(U$7-PadP$76)") (class "Default")
      (node (ref "U$7") (pin "P$76") (pinfunction "P$76_P$76") (pintype "bidirectional"))
    )
    (net (code "141") (name "unconnected-(U$7-PadP$91)") (class "Default")
      (node (ref "U$7") (pin "P$91") (pinfunction "P$91_P$91") (pintype "bidirectional"))
    )
    (net (code "142") (name "unconnected-(U$7-PadP$92)") (class "Default")
      (node (ref "U$7") (pin "P$92") (pinfunction "P$92_P$92") (pintype "bidirectional"))
    )
    (net (code "143") (name "unconnected-(U$7-PadP$95)") (class "Default")
      (node (ref "U$7") (pin "P$95") (pinfunction "P$95_P$95") (pintype "bidirectional"))
    )
    (net (code "144") (name "unconnected-(U$7-PadP$96)") (class "Default")
      (node (ref "U$7") (pin "P$96") (pinfunction "P$96_P$96") (pintype "bidirectional"))
    )
    (net (code "145") (name "unconnected-(U$7-RAHS_GND-PadP$94)") (class "Default")
      (node (ref "U$7") (pin "P$94") (pinfunction "RAHS_GND_P$94") (pintype "bidirectional"))
    )
    (net (code "146") (name "unconnected-(U$7-RAHS_VBAT-PadP$93)") (class "Default")
      (node (ref "U$7") (pin "P$93") (pinfunction "RAHS_VBAT_P$93") (pintype "bidirectional"))
    )
  )
)
